# alarmclock5.net
KiCad netlist of a schematic drawn in EAGLE
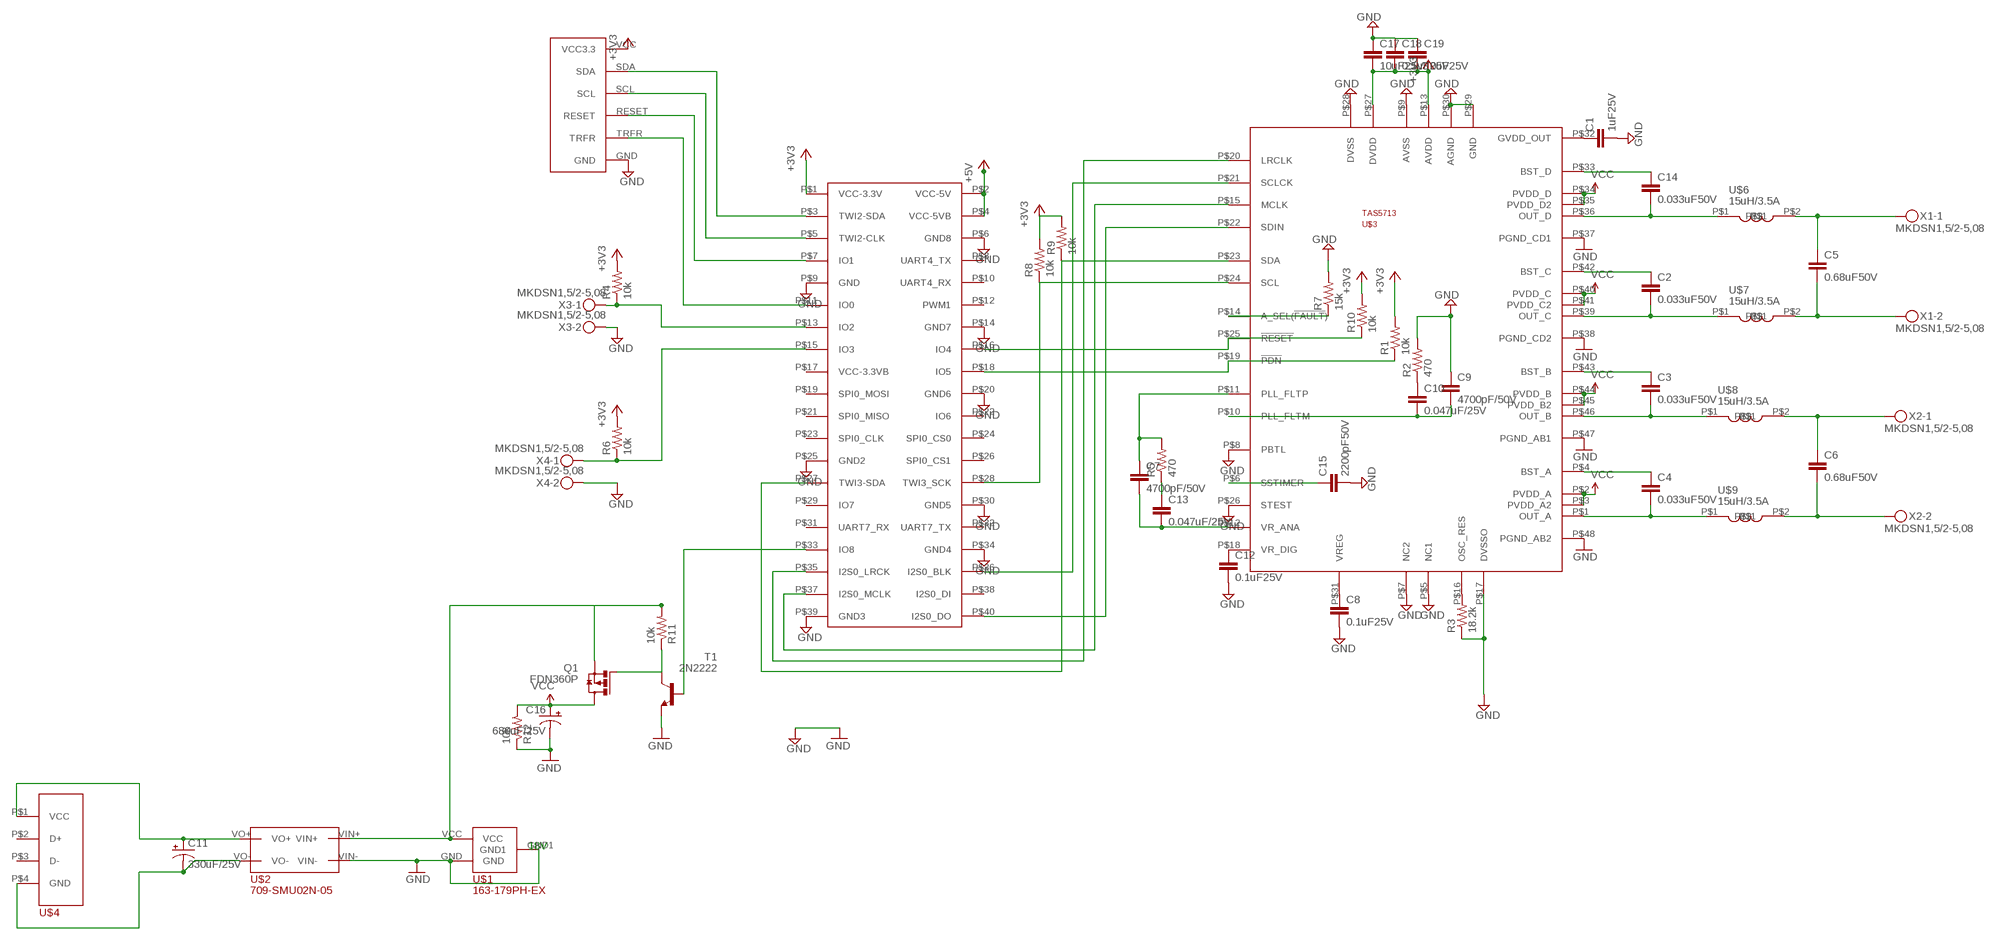
[diagram p0: schematic, sheet 1]

(export (version "E")
  (design (tool "Eeschema 10.0.6"))
  (components
    (comp (ref "C1")
      (value "1uF25V")
      (footprint "eagle-import:0603-CAP")
      (libsource (lib "eagle-import") (part "CAP0603-CAP"))
    )
    (comp (ref "C2")
      (value "0.033uF50V")
      (footprint "eagle-import:0603-CAP")
      (libsource (lib "eagle-import") (part "CAP0603-CAP"))
    )
    (comp (ref "C3")
      (value "0.033uF50V")
      (footprint "eagle-import:0603-CAP")
      (libsource (lib "eagle-import") (part "CAP0603-CAP"))
    )
    (comp (ref "C4")
      (value "0.033uF50V")
      (footprint "eagle-import:0603-CAP")
      (libsource (lib "eagle-import") (part "CAP0603-CAP"))
    )
    (comp (ref "C5")
      (value "0.68uF50V")
      (footprint "eagle-import:0603-CAP")
      (libsource (lib "eagle-import") (part "CAP0603-CAP"))
    )
    (comp (ref "C6")
      (value "0.68uF50V")
      (footprint "eagle-import:0603-CAP")
      (libsource (lib "eagle-import") (part "CAP0603-CAP"))
    )
    (comp (ref "C7")
      (value "4700pF/50V")
      (footprint "eagle-import:0603-CAP")
      (libsource (lib "eagle-import") (part "CAP0603-CAP"))
    )
    (comp (ref "C8")
      (value "0.1uF25V")
      (footprint "eagle-import:0603-CAP")
      (libsource (lib "eagle-import") (part "CAP0603-CAP"))
    )
    (comp (ref "C9")
      (value "4700pF/50V")
      (footprint "eagle-import:0603-CAP")
      (libsource (lib "eagle-import") (part "CAP0603-CAP"))
    )
    (comp (ref "C10")
      (value "0.047uF/25V")
      (footprint "eagle-import:0603-CAP")
      (libsource (lib "eagle-import") (part "CAP0603-CAP"))
    )
    (comp (ref "C11")
      (value "330uF/25V")
      (footprint "eagle-import:CPOL-RADIAL-10UF-25V")
      (libsource (lib "eagle-import") (part "CAP_POLPTH2"))
    )
    (comp (ref "C12")
      (value "0.1uF25V")
      (footprint "eagle-import:0603-CAP")
      (libsource (lib "eagle-import") (part "CAP0603-CAP"))
    )
    (comp (ref "C13")
      (value "0.047uF/25V")
      (footprint "eagle-import:0603-CAP")
      (libsource (lib "eagle-import") (part "CAP0603-CAP"))
    )
    (comp (ref "C14")
      (value "0.033uF50V")
      (footprint "eagle-import:0603-CAP")
      (libsource (lib "eagle-import") (part "CAP0603-CAP"))
    )
    (comp (ref "C15")
      (value "2200pF50V")
      (footprint "eagle-import:0603-CAP")
      (libsource (lib "eagle-import") (part "CAP0603-CAP"))
    )
    (comp (ref "C16")
      (value "680uF/25V")
      (footprint "eagle-import:CPOL-RADIAL-10UF-25V")
      (libsource (lib "eagle-import") (part "CAP_POLPTH2"))
    )
    (comp (ref "C17")
      (value "10uF25V")
      (footprint "eagle-import:0603-CAP")
      (libsource (lib "eagle-import") (part "CAP0603-CAP"))
    )
    (comp (ref "C18")
      (value "0.1uF25V")
      (footprint "eagle-import:0603-CAP")
      (libsource (lib "eagle-import") (part "CAP0603-CAP"))
    )
    (comp (ref "C19")
      (value "10uF25V")
      (footprint "eagle-import:0603-CAP")
      (libsource (lib "eagle-import") (part "CAP0603-CAP"))
    )
    (comp (ref "Q1")
      (value "FDN360P")
      (footprint "eagle-import:SUPER-SOT3")
      (libsource (lib "eagle-import") (part "FDN360P"))
    )
    (comp (ref "R1")
      (value "10k")
      (footprint "eagle-import:0603-RES")
      (libsource (lib "eagle-import") (part "RESISTOR0603-RES"))
    )
    (comp (ref "R2")
      (value "470")
      (footprint "eagle-import:0603-RES")
      (libsource (lib "eagle-import") (part "RESISTOR0603-RES"))
    )
    (comp (ref "R3")
      (value "18.2k")
      (footprint "eagle-import:0603-RES")
      (libsource (lib "eagle-import") (part "RESISTOR0603-RES"))
    )
    (comp (ref "R4")
      (value "10k")
      (footprint "eagle-import:0603-RES")
      (libsource (lib "eagle-import") (part "RESISTOR0603-RES"))
    )
    (comp (ref "R5")
      (value "470")
      (footprint "eagle-import:0603-RES")
      (libsource (lib "eagle-import") (part "RESISTOR0603-RES"))
    )
    (comp (ref "R6")
      (value "10k")
      (footprint "eagle-import:0603-RES")
      (libsource (lib "eagle-import") (part "RESISTOR0603-RES"))
    )
    (comp (ref "R7")
      (value "15k")
      (footprint "eagle-import:0603-RES")
      (libsource (lib "eagle-import") (part "RESISTOR0603-RES"))
    )
    (comp (ref "R8")
      (value "10k")
      (footprint "eagle-import:0603-RES")
      (libsource (lib "eagle-import") (part "RESISTOR0603-RES"))
    )
    (comp (ref "R9")
      (value "10k")
      (footprint "eagle-import:0603-RES")
      (libsource (lib "eagle-import") (part "RESISTOR0603-RES"))
    )
    (comp (ref "R10")
      (value "10k")
      (footprint "eagle-import:0603-RES")
      (libsource (lib "eagle-import") (part "RESISTOR0603-RES"))
    )
    (comp (ref "R11")
      (value "10k")
      (footprint "eagle-import:0603-RES")
      (libsource (lib "eagle-import") (part "RESISTOR0603-RES"))
    )
    (comp (ref "R12")
      (value "10k")
      (footprint "eagle-import:0603-RES")
      (libsource (lib "eagle-import") (part "RESISTOR0603-RES"))
    )
    (comp (ref "T1")
      (value "2N2222")
      (footprint "eagle-import:TO18")
      (libsource (lib "eagle-import") (part "2N2222"))
    )
    (comp (ref "U$1")
      (value "163-179PH-EX")
      (footprint "eagle-import:163-179PH-EX_DIM")
      (libsource (lib "eagle-import") (part "163-179PH-EX"))
    )
    (comp (ref "U$2")
      (value "709-SMU02N-05")
      (footprint "eagle-import:709-SMU02N-05_DIM")
      (libsource (lib "eagle-import") (part "709-SMU02N-05"))
    )
    (comp (ref "U$3")
      (value "TAS5713")
      (footprint "eagle-import:TAS5713_DIM")
      (libsource (lib "eagle-import") (part "TAS5713"))
    )
    (comp (ref "U$4")
      (value "USB_TYPEA_CONNECTOR")
      (footprint "eagle-import:USB_DIM")
      (libsource (lib "eagle-import") (part "USB_TYPEA_CONNECTOR"))
    )
    (comp (ref "U$5")
      (value "BANANAPRO-CON6")
      (footprint "eagle-import:BANANAPRO-CON6_DIM")
      (libsource (lib "eagle-import") (part "BANANAPRO-CON6"))
    )
    (comp (ref "U$6")
      (value "15uH/3.5A")
      (footprint "eagle-import:MSS1260_DIM")
      (libsource (lib "eagle-import") (part "MSS1260INDUCTOR"))
    )
    (comp (ref "U$7")
      (value "15uH/3.5A")
      (footprint "eagle-import:MSS1260_DIM")
      (libsource (lib "eagle-import") (part "MSS1260INDUCTOR"))
    )
    (comp (ref "U$8")
      (value "15uH/3.5A")
      (footprint "eagle-import:MSS1260_DIM")
      (libsource (lib "eagle-import") (part "MSS1260INDUCTOR"))
    )
    (comp (ref "U$9")
      (value "15uH/3.5A")
      (footprint "eagle-import:MSS1260_DIM")
      (libsource (lib "eagle-import") (part "MSS1260INDUCTOR"))
    )
    (comp (ref "U$10")
      (value "SKYWRITER")
      (footprint "eagle-import:SKYWRITER_DIM")
      (libsource (lib "eagle-import") (part "SKYWRITER"))
    )
    (comp (ref "X1")
      (value "MKDSN1,5/2-5,08")
      (footprint "eagle-import:MKDSN1,5_2-5,08")
      (libsource (lib "eagle-import") (part "MKDSN1,5/2-5,08"))
    )
    (comp (ref "X2")
      (value "MKDSN1,5/2-5,08")
      (footprint "eagle-import:MKDSN1,5_2-5,08")
      (libsource (lib "eagle-import") (part "MKDSN1,5/2-5,08"))
    )
    (comp (ref "X3")
      (value "MKDSN1,5/2-5,08")
      (footprint "eagle-import:MKDSN1,5_2-5,08")
      (libsource (lib "eagle-import") (part "MKDSN1,5/2-5,08"))
    )
    (comp (ref "X4")
      (value "MKDSN1,5/2-5,08")
      (footprint "eagle-import:MKDSN1,5_2-5,08")
      (libsource (lib "eagle-import") (part "MKDSN1,5/2-5,08"))
    )
  )
  (nets
    (net (code "1") (name "+3V3") (class "Default")
      (node (ref "C17") (pin "2") (pinfunction "2_2") (pintype "passive"))
      (node (ref "C18") (pin "2") (pinfunction "2_2") (pintype "passive"))
      (node (ref "C19") (pin "2") (pinfunction "2_2") (pintype "passive"))
      (node (ref "R1") (pin "2") (pinfunction "2_2") (pintype "passive"))
      (node (ref "R10") (pin "2") (pinfunction "2_2") (pintype "passive"))
      (node (ref "R4") (pin "2") (pinfunction "2_2") (pintype "passive"))
      (node (ref "R6") (pin "2") (pinfunction "2_2") (pintype "passive"))
      (node (ref "R8") (pin "2") (pinfunction "2_2") (pintype "passive"))
      (node (ref "R9") (pin "2") (pinfunction "2_2") (pintype "passive"))
      (node (ref "U$10") (pin "VCC") (pinfunction "VCC3.3_VCC") (pintype "bidirectional"))
      (node (ref "U$3") (pin "P$13") (pinfunction "AVDD_P$13") (pintype "bidirectional"))
      (node (ref "U$3") (pin "P$27") (pinfunction "DVDD_P$27") (pintype "bidirectional"))
      (node (ref "U$5") (pin "P$1") (pinfunction "VCC-3.3V_P$1") (pintype "bidirectional"))
    )
    (net (code "2") (name "+5V") (class "Default")
      (node (ref "U$5") (pin "P$2") (pinfunction "VCC-5V_P$2") (pintype "bidirectional"))
      (node (ref "U$5") (pin "P$4") (pinfunction "VCC-5VB_P$4") (pintype "bidirectional"))
    )
    (net (code "3") (name "GND") (class "Default")
      (node (ref "C1") (pin "2") (pinfunction "2_2") (pintype "passive"))
      (node (ref "C12") (pin "2") (pinfunction "2_2") (pintype "passive"))
      (node (ref "C15") (pin "2") (pinfunction "2_2") (pintype "passive"))
      (node (ref "C16") (pin "2") (pinfunction "-_2") (pintype "passive"))
      (node (ref "C17") (pin "1") (pinfunction "1_1") (pintype "passive"))
      (node (ref "C18") (pin "1") (pinfunction "1_1") (pintype "passive"))
      (node (ref "C19") (pin "1") (pinfunction "1_1") (pintype "passive"))
      (node (ref "C8") (pin "2") (pinfunction "2_2") (pintype "passive"))
      (node (ref "C9") (pin "1") (pinfunction "1_1") (pintype "passive"))
      (node (ref "R12") (pin "1") (pinfunction "1_1") (pintype "passive"))
      (node (ref "R2") (pin "2") (pinfunction "2_2") (pintype "passive"))
      (node (ref "R3") (pin "1") (pinfunction "1_1") (pintype "passive"))
      (node (ref "R7") (pin "2") (pinfunction "2_2") (pintype "passive"))
      (node (ref "T1") (pin "1") (pinfunction "E_1") (pintype "passive"))
      (node (ref "U$1") (pin "GND") (pinfunction "GND_GND") (pintype "bidirectional"))
      (node (ref "U$1") (pin "GND1") (pinfunction "GND1_GND1") (pintype "bidirectional"))
      (node (ref "U$10") (pin "GND") (pinfunction "GND_GND") (pintype "bidirectional"))
      (node (ref "U$2") (pin "VIN-") (pinfunction "VIN-_VIN-") (pintype "bidirectional"))
      (node (ref "U$3") (pin "P$17") (pinfunction "DVSSO_P$17") (pintype "bidirectional"))
      (node (ref "U$3") (pin "P$26") (pinfunction "STEST_P$26") (pintype "bidirectional"))
      (node (ref "U$3") (pin "P$28") (pinfunction "DVSS_P$28") (pintype "bidirectional"))
      (node (ref "U$3") (pin "P$29") (pinfunction "GND_P$29") (pintype "bidirectional"))
      (node (ref "U$3") (pin "P$30") (pinfunction "AGND_P$30") (pintype "bidirectional"))
      (node (ref "U$3") (pin "P$37") (pinfunction "PGND_CD1_P$37") (pintype "bidirectional"))
      (node (ref "U$3") (pin "P$38") (pinfunction "PGND_CD2_P$38") (pintype "bidirectional"))
      (node (ref "U$3") (pin "P$47") (pinfunction "PGND_AB1_P$47") (pintype "bidirectional"))
      (node (ref "U$3") (pin "P$48") (pinfunction "PGND_AB2_P$48") (pintype "bidirectional"))
      (node (ref "U$3") (pin "P$5") (pinfunction "NC1_P$5") (pintype "bidirectional"))
      (node (ref "U$3") (pin "P$7") (pinfunction "NC2_P$7") (pintype "bidirectional"))
      (node (ref "U$3") (pin "P$8") (pinfunction "PBTL_P$8") (pintype "bidirectional"))
      (node (ref "U$3") (pin "P$9") (pinfunction "AVSS_P$9") (pintype "bidirectional"))
      (node (ref "U$5") (pin "P$14") (pinfunction "GND7_P$14") (pintype "bidirectional"))
      (node (ref "U$5") (pin "P$20") (pinfunction "GND6_P$20") (pintype "bidirectional"))
      (node (ref "U$5") (pin "P$25") (pinfunction "GND2_P$25") (pintype "bidirectional"))
      (node (ref "U$5") (pin "P$30") (pinfunction "GND5_P$30") (pintype "bidirectional"))
      (node (ref "U$5") (pin "P$34") (pinfunction "GND4_P$34") (pintype "bidirectional"))
      (node (ref "U$5") (pin "P$39") (pinfunction "GND3_P$39") (pintype "bidirectional"))
      (node (ref "U$5") (pin "P$6") (pinfunction "GND8_P$6") (pintype "bidirectional"))
      (node (ref "U$5") (pin "P$9") (pinfunction "GND_P$9") (pintype "bidirectional"))
      (node (ref "X3") (pin "2") (pinfunction "KL_2") (pintype "passive"))
      (node (ref "X4") (pin "2") (pinfunction "KL_2") (pintype "passive"))
    )
    (net (code "4") (name "Net-(C10-Pad1)") (class "Default")
      (node (ref "C10") (pin "1") (pinfunction "1_1") (pintype "passive"))
      (node (ref "R2") (pin "1") (pinfunction "1_1") (pintype "passive"))
    )
    (net (code "5") (name "Net-(C11-+)") (class "Default")
      (node (ref "C11") (pin "1") (pinfunction "+_1") (pintype "passive"))
      (node (ref "U$2") (pin "VO+") (pinfunction "VO+_VO+") (pintype "bidirectional"))
      (node (ref "U$4") (pin "P$1") (pinfunction "VCC_P$1") (pintype "bidirectional"))
    )
    (net (code "6") (name "Net-(C11--)") (class "Default")
      (node (ref "C11") (pin "2") (pinfunction "-_2") (pintype "passive"))
      (node (ref "U$2") (pin "VO-") (pinfunction "VO-_VO-") (pintype "bidirectional"))
      (node (ref "U$4") (pin "P$4") (pinfunction "GND_P$4") (pintype "bidirectional"))
    )
    (net (code "7") (name "Net-(C13-Pad1)") (class "Default")
      (node (ref "C13") (pin "1") (pinfunction "1_1") (pintype "passive"))
      (node (ref "R5") (pin "1") (pinfunction "1_1") (pintype "passive"))
    )
    (net (code "8") (name "Net-(Q1-G)") (class "Default")
      (node (ref "Q1") (pin "1") (pinfunction "G_1") (pintype "passive"))
      (node (ref "R11") (pin "1") (pinfunction "1_1") (pintype "passive"))
      (node (ref "T1") (pin "3") (pinfunction "C_3") (pintype "passive"))
    )
    (net (code "9") (name "Net-(Q1-S)") (class "Default")
      (node (ref "Q1") (pin "2") (pinfunction "S_2") (pintype "passive"))
      (node (ref "R11") (pin "2") (pinfunction "2_2") (pintype "passive"))
      (node (ref "U$1") (pin "VCC") (pinfunction "VCC_VCC") (pintype "bidirectional"))
      (node (ref "U$2") (pin "VIN+") (pinfunction "VIN+_VIN+") (pintype "bidirectional"))
    )
    (net (code "10") (name "Net-(T1-B)") (class "Default")
      (node (ref "T1") (pin "2") (pinfunction "B_2") (pintype "passive"))
      (node (ref "U$5") (pin "P$33") (pinfunction "IO8_P$33") (pintype "bidirectional"))
    )
    (net (code "11") (name "Net-(U$3-A_SEL(~{FAULT}))") (class "Default")
      (node (ref "R7") (pin "1") (pinfunction "1_1") (pintype "passive"))
      (node (ref "U$3") (pin "P$14") (pinfunction "A_SEL(~{FAULT})_P$14") (pintype "bidirectional"))
    )
    (net (code "12") (name "Net-(U$3-BST_A)") (class "Default")
      (node (ref "C4") (pin "1") (pinfunction "1_1") (pintype "passive"))
      (node (ref "U$3") (pin "P$4") (pinfunction "BST_A_P$4") (pintype "bidirectional"))
    )
    (net (code "13") (name "Net-(U$3-BST_B)") (class "Default")
      (node (ref "C3") (pin "1") (pinfunction "1_1") (pintype "passive"))
      (node (ref "U$3") (pin "P$43") (pinfunction "BST_B_P$43") (pintype "bidirectional"))
    )
    (net (code "14") (name "Net-(U$3-BST_C)") (class "Default")
      (node (ref "C2") (pin "1") (pinfunction "1_1") (pintype "passive"))
      (node (ref "U$3") (pin "P$42") (pinfunction "BST_C_P$42") (pintype "bidirectional"))
    )
    (net (code "15") (name "Net-(U$3-BST_D)") (class "Default")
      (node (ref "C14") (pin "1") (pinfunction "1_1") (pintype "passive"))
      (node (ref "U$3") (pin "P$33") (pinfunction "BST_D_P$33") (pintype "bidirectional"))
    )
    (net (code "16") (name "Net-(U$3-GVDD_OUT)") (class "Default")
      (node (ref "C1") (pin "1") (pinfunction "1_1") (pintype "passive"))
      (node (ref "U$3") (pin "P$32") (pinfunction "GVDD_OUT_P$32") (pintype "bidirectional"))
    )
    (net (code "17") (name "Net-(U$3-LRCLK)") (class "Default")
      (node (ref "U$3") (pin "P$20") (pinfunction "LRCLK_P$20") (pintype "bidirectional"))
      (node (ref "U$5") (pin "P$35") (pinfunction "I2S0_LRCK_P$35") (pintype "bidirectional"))
    )
    (net (code "18") (name "Net-(U$3-MCLK)") (class "Default")
      (node (ref "U$3") (pin "P$15") (pinfunction "MCLK_P$15") (pintype "bidirectional"))
      (node (ref "U$5") (pin "P$37") (pinfunction "I2S0_MCLK_P$37") (pintype "bidirectional"))
    )
    (net (code "19") (name "Net-(U$3-OSC_RES)") (class "Default")
      (node (ref "R3") (pin "2") (pinfunction "2_2") (pintype "passive"))
      (node (ref "U$3") (pin "P$16") (pinfunction "OSC_RES_P$16") (pintype "bidirectional"))
    )
    (net (code "20") (name "Net-(U$3-OUT_A)") (class "Default")
      (node (ref "C4") (pin "2") (pinfunction "2_2") (pintype "passive"))
      (node (ref "U$3") (pin "P$1") (pinfunction "OUT_A_P$1") (pintype "bidirectional"))
      (node (ref "U$9") (pin "P$1") (pinfunction "P$1_P$1") (pintype "bidirectional"))
    )
    (net (code "21") (name "Net-(U$3-OUT_B)") (class "Default")
      (node (ref "C3") (pin "2") (pinfunction "2_2") (pintype "passive"))
      (node (ref "U$3") (pin "P$46") (pinfunction "OUT_B_P$46") (pintype "bidirectional"))
      (node (ref "U$8") (pin "P$1") (pinfunction "P$1_P$1") (pintype "bidirectional"))
    )
    (net (code "22") (name "Net-(U$3-OUT_C)") (class "Default")
      (node (ref "C2") (pin "2") (pinfunction "2_2") (pintype "passive"))
      (node (ref "U$3") (pin "P$39") (pinfunction "OUT_C_P$39") (pintype "bidirectional"))
      (node (ref "U$7") (pin "P$1") (pinfunction "P$1_P$1") (pintype "bidirectional"))
    )
    (net (code "23") (name "Net-(U$3-OUT_D)") (class "Default")
      (node (ref "C14") (pin "2") (pinfunction "2_2") (pintype "passive"))
      (node (ref "U$3") (pin "P$36") (pinfunction "OUT_D_P$36") (pintype "bidirectional"))
      (node (ref "U$6") (pin "P$1") (pinfunction "P$1_P$1") (pintype "bidirectional"))
    )
    (net (code "24") (name "Net-(U$3-PLL_FLTM)") (class "Default")
      (node (ref "C10") (pin "2") (pinfunction "2_2") (pintype "passive"))
      (node (ref "C9") (pin "2") (pinfunction "2_2") (pintype "passive"))
      (node (ref "U$3") (pin "P$10") (pinfunction "PLL_FLTM_P$10") (pintype "bidirectional"))
    )
    (net (code "25") (name "Net-(U$3-PLL_FLTP)") (class "Default")
      (node (ref "C7") (pin "1") (pinfunction "1_1") (pintype "passive"))
      (node (ref "R5") (pin "2") (pinfunction "2_2") (pintype "passive"))
      (node (ref "U$3") (pin "P$11") (pinfunction "PLL_FLTP_P$11") (pintype "bidirectional"))
    )
    (net (code "26") (name "Net-(U$3-SCL)") (class "Default")
      (node (ref "R8") (pin "1") (pinfunction "1_1") (pintype "passive"))
      (node (ref "U$3") (pin "P$24") (pinfunction "SCL_P$24") (pintype "bidirectional"))
      (node (ref "U$5") (pin "P$28") (pinfunction "TWI3_SCK_P$28") (pintype "bidirectional"))
    )
    (net (code "27") (name "Net-(U$3-SCLCK)") (class "Default")
      (node (ref "U$3") (pin "P$21") (pinfunction "SCLCK_P$21") (pintype "bidirectional"))
      (node (ref "U$5") (pin "P$36") (pinfunction "I2S0_BLK_P$36") (pintype "bidirectional"))
    )
    (net (code "28") (name "Net-(U$3-SDA)") (class "Default")
      (node (ref "R9") (pin "1") (pinfunction "1_1") (pintype "passive"))
      (node (ref "U$3") (pin "P$23") (pinfunction "SDA_P$23") (pintype "bidirectional"))
      (node (ref "U$5") (pin "P$27") (pinfunction "TWI3-SDA_P$27") (pintype "bidirectional"))
    )
    (net (code "29") (name "Net-(U$3-SDIN)") (class "Default")
      (node (ref "U$3") (pin "P$22") (pinfunction "SDIN_P$22") (pintype "bidirectional"))
      (node (ref "U$5") (pin "P$40") (pinfunction "I2S0_DO_P$40") (pintype "bidirectional"))
    )
    (net (code "30") (name "Net-(U$3-SSTIMER)") (class "Default")
      (node (ref "C15") (pin "1") (pinfunction "1_1") (pintype "passive"))
      (node (ref "U$3") (pin "P$6") (pinfunction "SSTIMER_P$6") (pintype "bidirectional"))
    )
    (net (code "31") (name "Net-(U$3-VREG)") (class "Default")
      (node (ref "C8") (pin "1") (pinfunction "1_1") (pintype "passive"))
      (node (ref "U$3") (pin "P$31") (pinfunction "VREG_P$31") (pintype "bidirectional"))
    )
    (net (code "32") (name "Net-(U$3-VR_ANA)") (class "Default")
      (node (ref "C13") (pin "2") (pinfunction "2_2") (pintype "passive"))
      (node (ref "C7") (pin "2") (pinfunction "2_2") (pintype "passive"))
      (node (ref "U$3") (pin "P$12") (pinfunction "VR_ANA_P$12") (pintype "bidirectional"))
    )
    (net (code "33") (name "Net-(U$3-VR_DIG)") (class "Default")
      (node (ref "C12") (pin "1") (pinfunction "1_1") (pintype "passive"))
      (node (ref "U$3") (pin "P$18") (pinfunction "VR_DIG_P$18") (pintype "bidirectional"))
    )
    (net (code "34") (name "Net-(U$3-~{PDN})") (class "Default")
      (node (ref "R1") (pin "1") (pinfunction "1_1") (pintype "passive"))
      (node (ref "U$3") (pin "P$19") (pinfunction "~{PDN}_P$19") (pintype "bidirectional"))
      (node (ref "U$5") (pin "P$18") (pinfunction "IO5_P$18") (pintype "bidirectional"))
    )
    (net (code "35") (name "Net-(U$3-~{RESET})") (class "Default")
      (node (ref "R10") (pin "1") (pinfunction "1_1") (pintype "passive"))
      (node (ref "U$3") (pin "P$25") (pinfunction "~{RESET}_P$25") (pintype "bidirectional"))
      (node (ref "U$5") (pin "P$16") (pinfunction "IO4_P$16") (pintype "bidirectional"))
    )
    (net (code "36") (name "Net-(U$5-IO0)") (class "Default")
      (node (ref "U$10") (pin "TRFR") (pinfunction "TRFR_TRFR") (pintype "bidirectional"))
      (node (ref "U$5") (pin "P$11") (pinfunction "IO0_P$11") (pintype "bidirectional"))
    )
    (net (code "37") (name "Net-(U$5-IO1)") (class "Default")
      (node (ref "U$10") (pin "RESET") (pinfunction "RESET_RESET") (pintype "bidirectional"))
      (node (ref "U$5") (pin "P$7") (pinfunction "IO1_P$7") (pintype "bidirectional"))
    )
    (net (code "38") (name "Net-(U$5-IO2)") (class "Default")
      (node (ref "R4") (pin "1") (pinfunction "1_1") (pintype "passive"))
      (node (ref "U$5") (pin "P$13") (pinfunction "IO2_P$13") (pintype "bidirectional"))
      (node (ref "X3") (pin "1") (pinfunction "KL_1") (pintype "passive"))
    )
    (net (code "39") (name "Net-(U$5-IO3)") (class "Default")
      (node (ref "R6") (pin "1") (pinfunction "1_1") (pintype "passive"))
      (node (ref "U$5") (pin "P$15") (pinfunction "IO3_P$15") (pintype "bidirectional"))
      (node (ref "X4") (pin "1") (pinfunction "KL_1") (pintype "passive"))
    )
    (net (code "40") (name "Net-(U$5-TWI2-CLK)") (class "Default")
      (node (ref "U$10") (pin "SCL") (pinfunction "SCL_SCL") (pintype "bidirectional"))
      (node (ref "U$5") (pin "P$5") (pinfunction "TWI2-CLK_P$5") (pintype "bidirectional"))
    )
    (net (code "41") (name "Net-(U$5-TWI2-SDA)") (class "Default")
      (node (ref "U$10") (pin "SDA") (pinfunction "SDA_SDA") (pintype "bidirectional"))
      (node (ref "U$5") (pin "P$3") (pinfunction "TWI2-SDA_P$3") (pintype "bidirectional"))
    )
    (net (code "42") (name "Net-(X1A-KL)") (class "Default")
      (node (ref "C5") (pin "1") (pinfunction "1_1") (pintype "passive"))
      (node (ref "U$6") (pin "P$2") (pinfunction "P$2_P$2") (pintype "bidirectional"))
      (node (ref "X1") (pin "1") (pinfunction "KL_1") (pintype "passive"))
    )
    (net (code "43") (name "Net-(X1B-KL)") (class "Default")
      (node (ref "C5") (pin "2") (pinfunction "2_2") (pintype "passive"))
      (node (ref "U$7") (pin "P$2") (pinfunction "P$2_P$2") (pintype "bidirectional"))
      (node (ref "X1") (pin "2") (pinfunction "KL_2") (pintype "passive"))
    )
    (net (code "44") (name "Net-(X2A-KL)") (class "Default")
      (node (ref "C6") (pin "1") (pinfunction "1_1") (pintype "passive"))
      (node (ref "U$8") (pin "P$2") (pinfunction "P$2_P$2") (pintype "bidirectional"))
      (node (ref "X2") (pin "1") (pinfunction "KL_1") (pintype "passive"))
    )
    (net (code "45") (name "Net-(X2B-KL)") (class "Default")
      (node (ref "C6") (pin "2") (pinfunction "2_2") (pintype "passive"))
      (node (ref "U$9") (pin "P$2") (pinfunction "P$2_P$2") (pintype "bidirectional"))
      (node (ref "X2") (pin "2") (pinfunction "KL_2") (pintype "passive"))
    )
    (net (code "46") (name "VCC") (class "Default")
      (node (ref "C16") (pin "1") (pinfunction "+_1") (pintype "passive"))
      (node (ref "Q1") (pin "3") (pinfunction "D_3") (pintype "passive"))
      (node (ref "R12") (pin "2") (pinfunction "2_2") (pintype "passive"))
      (node (ref "U$3") (pin "P$2") (pinfunction "PVDD_A_P$2") (pintype "bidirectional"))
      (node (ref "U$3") (pin "P$3") (pinfunction "PVDD_A2_P$3") (pintype "bidirectional"))
      (node (ref "U$3") (pin "P$34") (pinfunction "PVDD_D_P$34") (pintype "bidirectional"))
      (node (ref "U$3") (pin "P$35") (pinfunction "PVDD_D2_P$35") (pintype "bidirectional"))
      (node (ref "U$3") (pin "P$40") (pinfunction "PVDD_C_P$40") (pintype "bidirectional"))
      (node (ref "U$3") (pin "P$41") (pinfunction "PVDD_C2_P$41") (pintype "bidirectional"))
      (node (ref "U$3") (pin "P$44") (pinfunction "PVDD_B_P$44") (pintype "bidirectional"))
      (node (ref "U$3") (pin "P$45") (pinfunction "PVDD_B2_P$45") (pintype "bidirectional"))
    )
    (net (code "47") (name "unconnected-(U$4-D+-PadP$2)") (class "Default")
      (node (ref "U$4") (pin "P$2") (pinfunction "D+_P$2") (pintype "bidirectional"))
    )
    (net (code "48") (name "unconnected-(U$4-D--PadP$3)") (class "Default")
      (node (ref "U$4") (pin "P$3") (pinfunction "D-_P$3") (pintype "bidirectional"))
    )
    (net (code "49") (name "unconnected-(U$5-I2S0_DI-PadP$38)") (class "Default")
      (node (ref "U$5") (pin "P$38") (pinfunction "I2S0_DI_P$38") (pintype "bidirectional"))
    )
    (net (code "50") (name "unconnected-(U$5-IO6-PadP$22)") (class "Default")
      (node (ref "U$5") (pin "P$22") (pinfunction "IO6_P$22") (pintype "bidirectional"))
    )
    (net (code "51") (name "unconnected-(U$5-IO7-PadP$29)") (class "Default")
      (node (ref "U$5") (pin "P$29") (pinfunction "IO7_P$29") (pintype "bidirectional"))
    )
    (net (code "52") (name "unconnected-(U$5-PWM1-PadP$12)") (class "Default")
      (node (ref "U$5") (pin "P$12") (pinfunction "PWM1_P$12") (pintype "bidirectional"))
    )
    (net (code "53") (name "unconnected-(U$5-SPI0_CLK-PadP$23)") (class "Default")
      (node (ref "U$5") (pin "P$23") (pinfunction "SPI0_CLK_P$23") (pintype "bidirectional"))
    )
    (net (code "54") (name "unconnected-(U$5-SPI0_CS0-PadP$24)") (class "Default")
      (node (ref "U$5") (pin "P$24") (pinfunction "SPI0_CS0_P$24") (pintype "bidirectional"))
    )
    (net (code "55") (name "unconnected-(U$5-SPI0_CS1-PadP$26)") (class "Default")
      (node (ref "U$5") (pin "P$26") (pinfunction "SPI0_CS1_P$26") (pintype "bidirectional"))
    )
    (net (code "56") (name "unconnected-(U$5-SPI0_MISO-PadP$21)") (class "Default")
      (node (ref "U$5") (pin "P$21") (pinfunction "SPI0_MISO_P$21") (pintype "bidirectional"))
    )
    (net (code "57") (name "unconnected-(U$5-SPI0_MOSI-PadP$19)") (class "Default")
      (node (ref "U$5") (pin "P$19") (pinfunction "SPI0_MOSI_P$19") (pintype "bidirectional"))
    )
    (net (code "58") (name "unconnected-(U$5-UART4_RX-PadP$10)") (class "Default")
      (node (ref "U$5") (pin "P$10") (pinfunction "UART4_RX_P$10") (pintype "bidirectional"))
    )
    (net (code "59") (name "unconnected-(U$5-UART4_TX-PadP$8)") (class "Default")
      (node (ref "U$5") (pin "P$8") (pinfunction "UART4_TX_P$8") (pintype "bidirectional"))
    )
    (net (code "60") (name "unconnected-(U$5-UART7_RX-PadP$31)") (class "Default")
      (node (ref "U$5") (pin "P$31") (pinfunction "UART7_RX_P$31") (pintype "bidirectional"))
    )
    (net (code "61") (name "unconnected-(U$5-UART7_TX-PadP$32)") (class "Default")
      (node (ref "U$5") (pin "P$32") (pinfunction "UART7_TX_P$32") (pintype "bidirectional"))
    )
    (net (code "62") (name "unconnected-(U$5-VCC-3.3VB-PadP$17)") (class "Default")
      (node (ref "U$5") (pin "P$17") (pinfunction "VCC-3.3VB_P$17") (pintype "bidirectional"))
    )
  )
)
